# Interfaces.net
KiCad netlist of a schematic drawn in Altium Designer
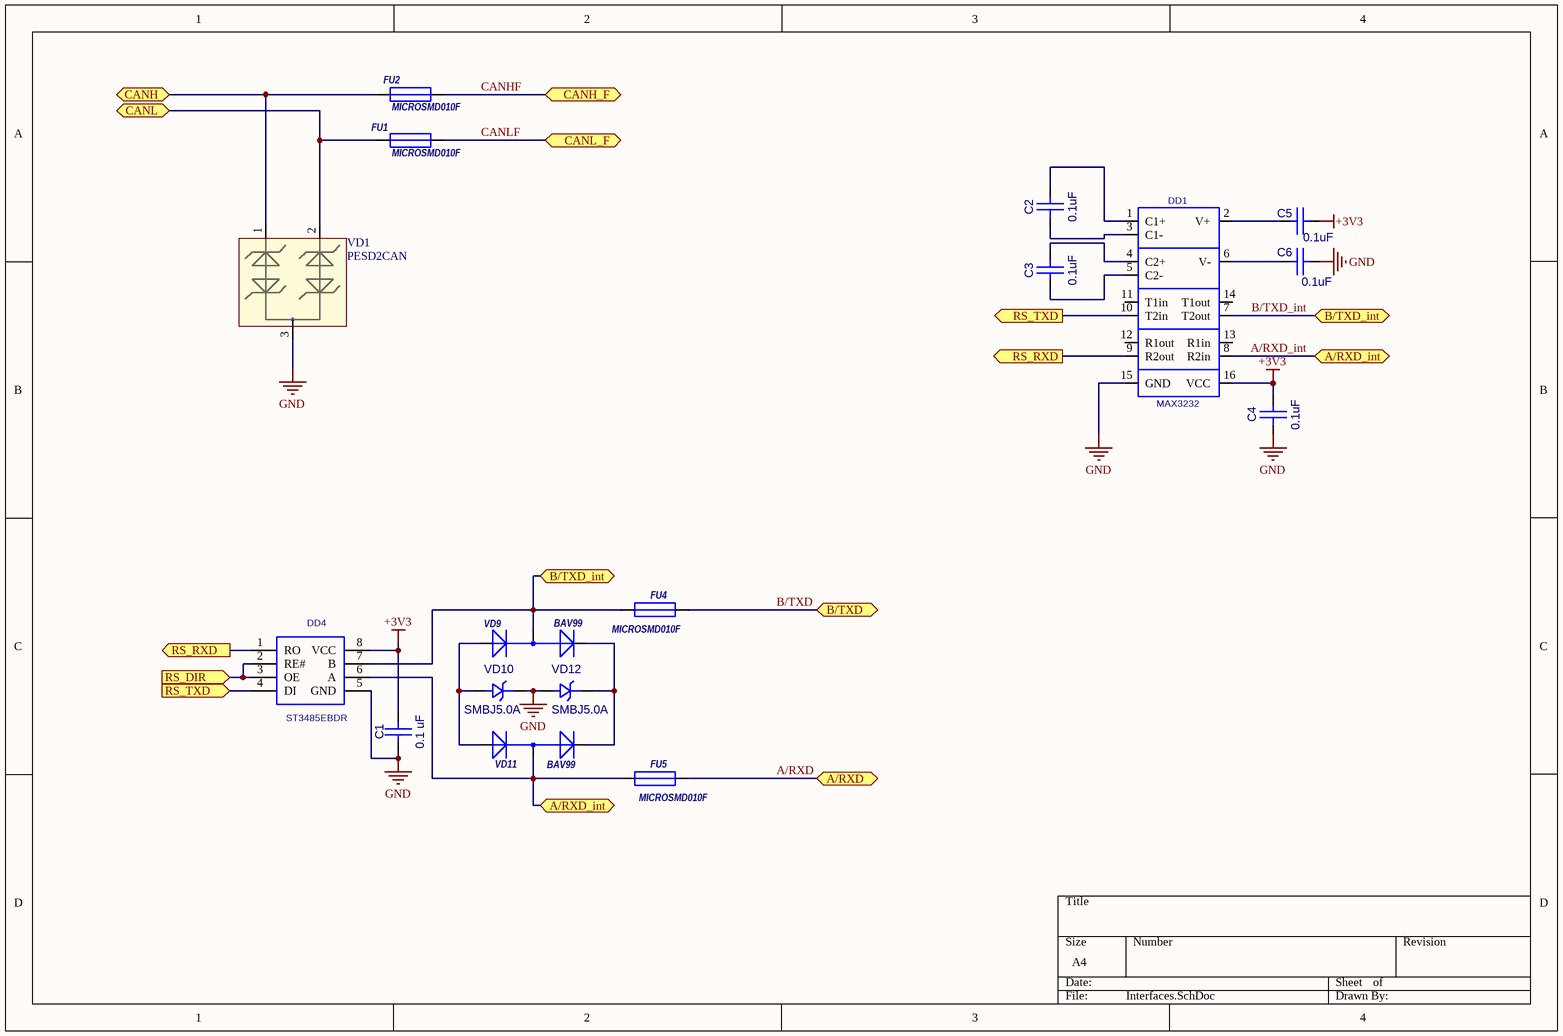
[diagram p0: Interfaces.SchDoc]

(export (version "E")
  (design (tool "Eeschema 10.0.6"))
  (components
    (comp (ref "C1")
      (value "0.1 uF")
      (footprint "CC0603-3M")
      (description "CC0603")
      (libsource (lib "*") (part "CC0603"))
    )
    (comp (ref "C2")
      (value "0.1uF")
      (footprint "CC0603-3M")
      (description "CC0603")
      (libsource (lib "gprs_modem") (part "CC0603"))
    )
    (comp (ref "C3")
      (value "0.1uF")
      (footprint "CC0603-3M")
      (description "CC0603")
      (libsource (lib "gprs_modem") (part "CC0603"))
    )
    (comp (ref "C4")
      (value "0.1uF")
      (footprint "CC0603-3M")
      (description "CC0603")
      (libsource (lib "gprs_modem") (part "CC0603"))
    )
    (comp (ref "C5")
      (value "0.1uF")
      (footprint "CC0603-3M")
      (description "CC0603")
      (libsource (lib "gprs_modem") (part "CC0603"))
    )
    (comp (ref "C6")
      (value "0.1uF")
      (footprint "CC0603-3M")
      (description "CC0603")
      (libsource (lib "gprs_modem") (part "CC0603"))
    )
    (comp (ref "DD1")
      (value "MAX3232")
      (footprint "SO16_M")
      (description "ST232BD/CD")
      (libsource (lib "gprs_modem") (part "ST232BD/CD"))
    )
    (comp (ref "DD4")
      (value "ST3485EBDR")
      (footprint "SO-8")
      (description "SP485")
      (libsource (lib "Schetchik") (part "SP485"))
    )
    (comp (ref "FU1")
      (value "MICROSMD010F")
      (footprint "RC1210")
      (description "MICROSMD")
      (libsource (lib "Schetchik") (part "MICROSMD"))
    )
    (comp (ref "FU2")
      (value "MICROSMD010F")
      (footprint "RC1210")
      (description "MICROSMD")
      (libsource (lib "Schetchik") (part "MICROSMD"))
    )
    (comp (ref "FU4")
      (value "MICROSMD010F")
      (footprint "RC1210")
      (description "MICROSMD")
      (libsource (lib "*") (part "MICROSMD"))
    )
    (comp (ref "FU5")
      (value "MICROSMD010F")
      (footprint "RC1210")
      (description "MICROSMD")
      (libsource (lib "*") (part "MICROSMD"))
    )
    (comp (ref "VD1")
      (value "PESD2CAN")
      (footprint "SOT-23(123)")
      (description "TVS for CAN")
      (libsource (lib "gprs_modem") (part "PESD2CAN"))
    )
    (comp (ref "VD9")
      (value "BAV99")
      (footprint "SOT-23(GSD)")
      (description "1.0 Ampere General Purpose Rectifier")
      (libsource (lib "gprs_modem") (part "BAV99"))
    )
    (comp (ref "VD10")
      (value "SMBJ5.0A")
      (footprint "SMB")
      (description "SMBJ")
      (libsource (lib "gprs_modem") (part "SMBJ"))
    )
    (comp (ref "VD11")
      (value "BAV99")
      (footprint "SOT-23(GSD)")
      (description "1.0 Ampere General Purpose Rectifier")
      (libsource (lib "gprs_modem") (part "BAV99"))
    )
    (comp (ref "VD12")
      (value "SMBJ5.0A")
      (footprint "SMB")
      (description "SMBJ")
      (libsource (lib "gprs_modem") (part "SMBJ"))
    )
  )
  (nets
    (net (code "1") (name "+3V3") (class "Default")
      (node (ref "C1") (pin "2") (pinfunction "B_2") (pintype "passive"))
      (node (ref "C4") (pin "2") (pinfunction "B_2") (pintype "passive"))
      (node (ref "C5") (pin "1") (pinfunction "A_1") (pintype "passive"))
      (node (ref "DD1") (pin "16") (pinfunction "VCC_16") (pintype "passive"))
      (node (ref "DD4") (pin "8") (pinfunction "VCC_8") (pintype "passive"))
    )
    (net (code "2") (name "/A{slash}RXD") (class "Default") (node (ref "FU5") (pin "1") (pintype "passive")))
    (net (code "3") (name "/A{slash}RXD_int") (class "Default")
      (node (ref "DD1") (pin "8") (pinfunction "R2in_8") (pintype "passive"))
      (node (ref "DD4") (pin "6") (pinfunction "A_6") (pintype "passive"))
      (node (ref "FU5") (pin "2") (pintype "passive"))
      (node (ref "VD11") (pin "3") (pinfunction "AK_3") (pintype "passive"))
    )
    (net (code "4") (name "/B{slash}TXD") (class "Default") (node (ref "FU4") (pin "1") (pintype "passive")))
    (net (code "5") (name "/B{slash}TXD_int") (class "Default")
      (node (ref "DD1") (pin "7") (pinfunction "T2out_7") (pintype "passive"))
      (node (ref "DD4") (pin "7") (pinfunction "B_7") (pintype "passive"))
      (node (ref "FU4") (pin "2") (pintype "passive"))
      (node (ref "VD9") (pin "3") (pinfunction "AK_3") (pintype "passive"))
    )
    (net (code "6") (name "/CANH") (class "Default")
      (node (ref "FU2") (pin "1") (pintype "passive"))
      (node (ref "VD1") (pin "1") (pinfunction "1_1") (pintype "passive"))
    )
    (net (code "7") (name "/CANHF") (class "Default") (node (ref "FU2") (pin "2") (pintype "passive")))
    (net (code "8") (name "/CANL") (class "Default")
      (node (ref "FU1") (pin "1") (pintype "passive"))
      (node (ref "VD1") (pin "2") (pinfunction "2_2") (pintype "passive"))
    )
    (net (code "9") (name "/CANLF") (class "Default") (node (ref "FU1") (pin "2") (pintype "passive")))
    (net (code "10") (name "/RS_DIR") (class "Default")
      (node (ref "DD4") (pin "2") (pinfunction "RE#_2") (pintype "passive"))
      (node (ref "DD4") (pin "3") (pinfunction "OE_3") (pintype "passive"))
    )
    (net (code "11") (name "/RS_RXD") (class "Default")
      (node (ref "DD1") (pin "9") (pinfunction "R2out_9") (pintype "passive"))
      (node (ref "DD4") (pin "1") (pinfunction "RO_1") (pintype "passive"))
    )
    (net (code "12") (name "/RS_TXD") (class "Default")
      (node (ref "DD1") (pin "10") (pinfunction "T2in_10") (pintype "passive"))
      (node (ref "DD4") (pin "4") (pinfunction "DI_4") (pintype "passive"))
    )
    (net (code "13") (name "GND") (class "Default")
      (node (ref "C1") (pin "1") (pinfunction "A_1") (pintype "passive"))
      (node (ref "C4") (pin "1") (pinfunction "A_1") (pintype "passive"))
      (node (ref "C6") (pin "1") (pinfunction "A_1") (pintype "passive"))
      (node (ref "DD1") (pin "15") (pinfunction "GND_15") (pintype "passive"))
      (node (ref "DD4") (pin "5") (pinfunction "GND_5") (pintype "passive"))
      (node (ref "VD1") (pin "3") (pinfunction "3_3") (pintype "passive"))
      (node (ref "VD10") (pin "2") (pinfunction "K_2") (pintype "passive"))
      (node (ref "VD12") (pin "1") (pinfunction "A_1") (pintype "passive"))
    )
    (net (code "14") (name "Net-(C2-A)") (class "Default")
      (node (ref "C2") (pin "1") (pinfunction "A_1") (pintype "passive"))
      (node (ref "DD1") (pin "3") (pinfunction "C1-_3") (pintype "passive"))
    )
    (net (code "15") (name "Net-(C2-B)") (class "Default")
      (node (ref "C2") (pin "2") (pinfunction "B_2") (pintype "passive"))
      (node (ref "DD1") (pin "1") (pinfunction "C1+_1") (pintype "passive"))
    )
    (net (code "16") (name "Net-(C3-A)") (class "Default")
      (node (ref "C3") (pin "1") (pinfunction "A_1") (pintype "passive"))
      (node (ref "DD1") (pin "5") (pinfunction "C2-_5") (pintype "passive"))
    )
    (net (code "17") (name "Net-(C3-B)") (class "Default")
      (node (ref "C3") (pin "2") (pinfunction "B_2") (pintype "passive"))
      (node (ref "DD1") (pin "4") (pinfunction "C2+_4") (pintype "passive"))
    )
    (net (code "18") (name "Net-(C5-B)") (class "Default")
      (node (ref "C5") (pin "2") (pinfunction "B_2") (pintype "passive"))
      (node (ref "DD1") (pin "2") (pinfunction "V+_2") (pintype "passive"))
    )
    (net (code "19") (name "Net-(C6-B)") (class "Default")
      (node (ref "C6") (pin "2") (pinfunction "B_2") (pintype "passive"))
      (node (ref "DD1") (pin "6") (pinfunction "V-_6") (pintype "passive"))
    )
    (net (code "20") (name "Net-(VD10-A)") (class "Default")
      (node (ref "VD10") (pin "1") (pinfunction "A_1") (pintype "passive"))
      (node (ref "VD11") (pin "1") (pinfunction "A_1") (pintype "passive"))
      (node (ref "VD9") (pin "1") (pinfunction "A_1") (pintype "passive"))
    )
    (net (code "21") (name "Net-(VD11-K)") (class "Default")
      (node (ref "VD11") (pin "2") (pinfunction "K_2") (pintype "passive"))
      (node (ref "VD12") (pin "2") (pinfunction "K_2") (pintype "passive"))
      (node (ref "VD9") (pin "2") (pinfunction "K_2") (pintype "passive"))
    )
    (net (code "22") (name "unconnected-(DD1-R1in-Pad13)") (class "Default")
      (node (ref "DD1") (pin "13") (pinfunction "R1in_13") (pintype "passive"))
    )
    (net (code "23") (name "unconnected-(DD1-R1out-Pad12)") (class "Default")
      (node (ref "DD1") (pin "12") (pinfunction "R1out_12") (pintype "passive"))
    )
    (net (code "24") (name "unconnected-(DD1-T1in-Pad11)") (class "Default")
      (node (ref "DD1") (pin "11") (pinfunction "T1in_11") (pintype "passive"))
    )
    (net (code "25") (name "unconnected-(DD1-T1out-Pad14)") (class "Default")
      (node (ref "DD1") (pin "14") (pinfunction "T1out_14") (pintype "passive"))
    )
  )
)
